# IR_Distance.net
KiCad netlist of a schematic drawn in EAGLE
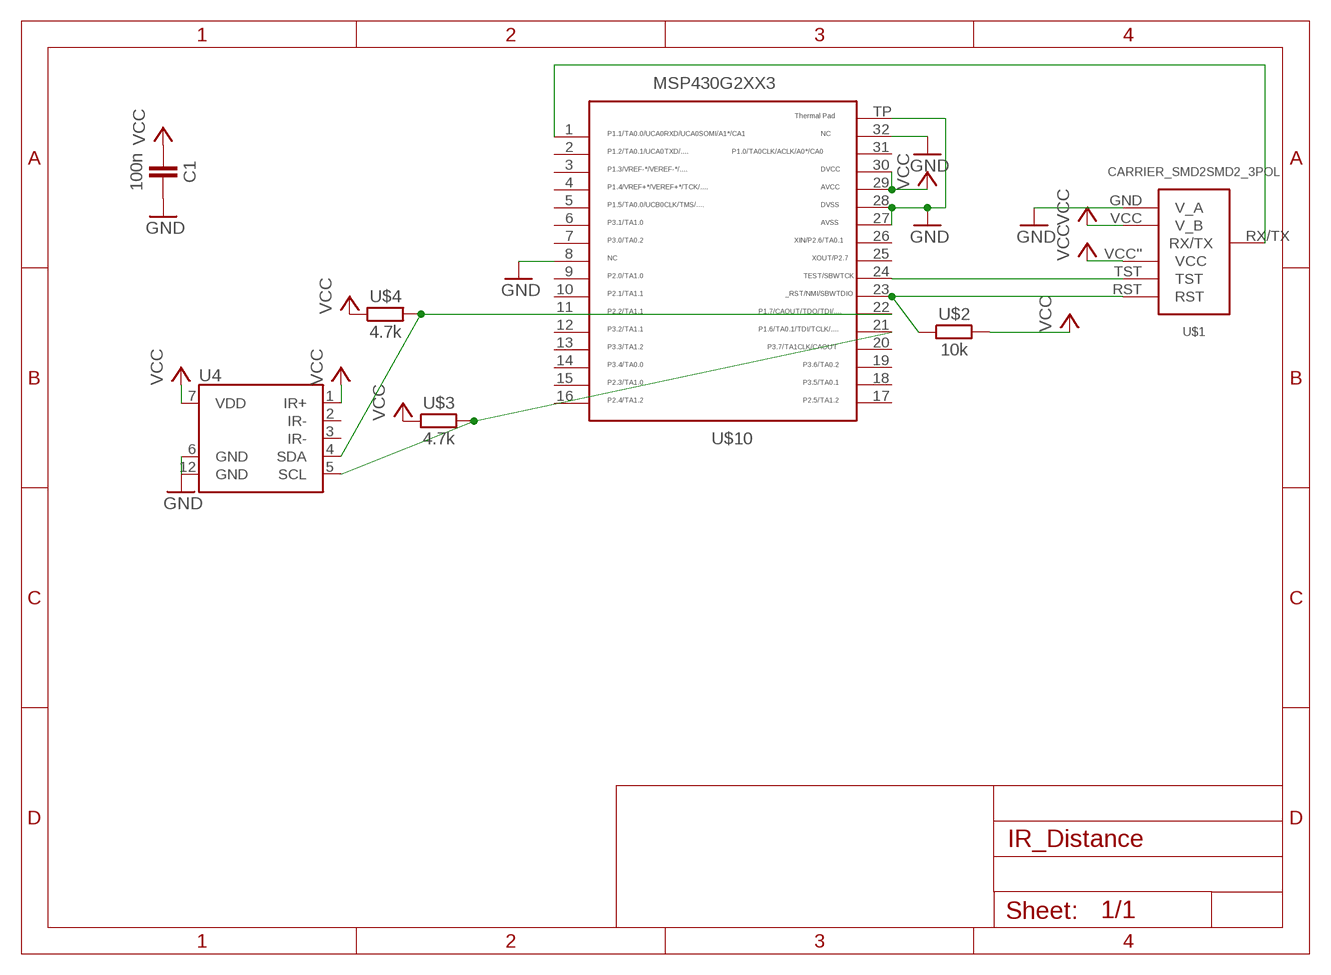
[diagram p0: schematic, sheet 1]

(export (version "E")
  (design (tool "Eeschema 10.0.6"))
  (components
    (comp (ref "C1")
      (value "100n")
      (footprint "eagle-import:603")
      (libsource (lib "eagle-import") (part "CAPACITOR"))
    )
    (comp (ref "U$1")
      (value "CARRIER_SMD2SMD2_3POL")
      (footprint "eagle-import:CARRIER_SMD2_3POL")
      (libsource (lib "eagle-import") (part "CARRIER_SMD2SMD2_3POL"))
    )
    (comp (ref "U$2")
      (value "10k")
      (footprint "eagle-import:603")
      (libsource (lib "eagle-import") (part "RESISTOR0603"))
    )
    (comp (ref "U$3")
      (value "4.7k")
      (footprint "eagle-import:603")
      (libsource (lib "eagle-import") (part "RESISTOR0603"))
    )
    (comp (ref "U$4")
      (value "4.7k")
      (footprint "eagle-import:603")
      (libsource (lib "eagle-import") (part "RESISTOR0603"))
    )
    (comp (ref "U$10")
      (value "MSP430G2553")
      (footprint "eagle-import:QFN32")
      (libsource (lib "eagle-import") (part "MSP430G2553"))
    )
    (comp (ref "U4")
      (value "VCNL4000")
      (footprint "eagle-import:VCNL4000")
      (libsource (lib "eagle-import") (part "VCNL4000"))
    )
  )
  (nets
    (net (code "1") (name "GND") (class "Default")
      (node (ref "C1") (pin "2") (pinfunction "2_2") (pintype "passive"))
      (node (ref "U$1") (pin "GND") (pinfunction "V_A_GND") (pintype "bidirectional"))
      (node (ref "U$10") (pin "27") (pinfunction "27_27") (pintype "bidirectional"))
      (node (ref "U$10") (pin "28") (pinfunction "28_28") (pintype "bidirectional"))
      (node (ref "U$10") (pin "32") (pinfunction "32_32") (pintype "bidirectional"))
      (node (ref "U$10") (pin "8") (pinfunction "8_8") (pintype "bidirectional"))
      (node (ref "U$10") (pin "TP") (pinfunction "TP_TP") (pintype "bidirectional"))
      (node (ref "U4") (pin "12") (pinfunction "GND_12") (pintype "bidirectional"))
      (node (ref "U4") (pin "6") (pinfunction "GND_6") (pintype "bidirectional"))
    )
    (net (code "2") (name "Net-(U$1-PadRST)") (class "Default")
      (node (ref "U$1") (pin "RST") (pinfunction "RST_RST") (pintype "bidirectional"))
      (node (ref "U$10") (pin "23") (pinfunction "23_23") (pintype "bidirectional"))
      (node (ref "U$2") (pin "1") (pinfunction "1_1") (pintype "passive"))
    )
    (net (code "3") (name "Net-(U$1-PadRX{slash}TX)") (class "Default")
      (node (ref "U$1") (pin "RX/TX") (pinfunction "RX/TX_RX/TX") (pintype "bidirectional"))
      (node (ref "U$10") (pin "1") (pinfunction "1_1") (pintype "bidirectional"))
    )
    (net (code "4") (name "Net-(U$1-PadTST)") (class "Default")
      (node (ref "U$1") (pin "TST") (pinfunction "TST_TST") (pintype "bidirectional"))
      (node (ref "U$10") (pin "24") (pinfunction "24_24") (pintype "bidirectional"))
    )
    (net (code "5") (name "Net-(U4-SCL)") (class "Default")
      (node (ref "U$10") (pin "21") (pinfunction "21_21") (pintype "bidirectional"))
      (node (ref "U$3") (pin "2") (pinfunction "2_2") (pintype "passive"))
      (node (ref "U4") (pin "5") (pinfunction "SCL_5") (pintype "bidirectional"))
    )
    (net (code "6") (name "Net-(U4-SDA)") (class "Default")
      (node (ref "U$10") (pin "22") (pinfunction "22_22") (pintype "bidirectional"))
      (node (ref "U$4") (pin "2") (pinfunction "2_2") (pintype "passive"))
      (node (ref "U4") (pin "4") (pinfunction "SDA_4") (pintype "bidirectional"))
    )
    (net (code "7") (name "VCC") (class "Default")
      (node (ref "C1") (pin "1") (pinfunction "1_1") (pintype "passive"))
      (node (ref "U$1") (pin "VCC") (pinfunction "V_B_VCC") (pintype "bidirectional"))
      (node (ref "U$1") (pin "VCC''") (pinfunction "VCC_VCC''") (pintype "bidirectional"))
      (node (ref "U$10") (pin "29") (pinfunction "29_29") (pintype "bidirectional"))
      (node (ref "U$10") (pin "30") (pinfunction "30_30") (pintype "bidirectional"))
      (node (ref "U$2") (pin "2") (pinfunction "2_2") (pintype "passive"))
      (node (ref "U$3") (pin "1") (pinfunction "1_1") (pintype "passive"))
      (node (ref "U$4") (pin "1") (pinfunction "1_1") (pintype "passive"))
      (node (ref "U4") (pin "1") (pinfunction "IR+_1") (pintype "bidirectional"))
      (node (ref "U4") (pin "7") (pinfunction "VDD_7") (pintype "bidirectional"))
    )
    (net (code "8") (name "unconnected-(U$10-Pad2)") (class "Default")
      (node (ref "U$10") (pin "2") (pinfunction "2_2") (pintype "bidirectional"))
    )
    (net (code "9") (name "unconnected-(U$10-Pad3)") (class "Default")
      (node (ref "U$10") (pin "3") (pinfunction "3_3") (pintype "bidirectional"))
    )
    (net (code "10") (name "unconnected-(U$10-Pad4)") (class "Default")
      (node (ref "U$10") (pin "4") (pinfunction "4_4") (pintype "bidirectional"))
    )
    (net (code "11") (name "unconnected-(U$10-Pad5)") (class "Default")
      (node (ref "U$10") (pin "5") (pinfunction "5_5") (pintype "bidirectional"))
    )
    (net (code "12") (name "unconnected-(U$10-Pad6)") (class "Default")
      (node (ref "U$10") (pin "6") (pinfunction "6_6") (pintype "bidirectional"))
    )
    (net (code "13") (name "unconnected-(U$10-Pad7)") (class "Default")
      (node (ref "U$10") (pin "7") (pinfunction "7_7") (pintype "bidirectional"))
    )
    (net (code "14") (name "unconnected-(U$10-Pad9)") (class "Default")
      (node (ref "U$10") (pin "9") (pinfunction "9_9") (pintype "bidirectional"))
    )
    (net (code "15") (name "unconnected-(U$10-Pad10)") (class "Default")
      (node (ref "U$10") (pin "10") (pinfunction "10_10") (pintype "bidirectional"))
    )
    (net (code "16") (name "unconnected-(U$10-Pad11)") (class "Default")
      (node (ref "U$10") (pin "11") (pinfunction "11_11") (pintype "bidirectional"))
    )
    (net (code "17") (name "unconnected-(U$10-Pad12)") (class "Default")
      (node (ref "U$10") (pin "12") (pinfunction "12_12") (pintype "bidirectional"))
    )
    (net (code "18") (name "unconnected-(U$10-Pad13)") (class "Default")
      (node (ref "U$10") (pin "13") (pinfunction "13_13") (pintype "bidirectional"))
    )
    (net (code "19") (name "unconnected-(U$10-Pad14)") (class "Default")
      (node (ref "U$10") (pin "14") (pinfunction "14_14") (pintype "bidirectional"))
    )
    (net (code "20") (name "unconnected-(U$10-Pad15)") (class "Default")
      (node (ref "U$10") (pin "15") (pinfunction "15_15") (pintype "bidirectional"))
    )
    (net (code "21") (name "unconnected-(U$10-Pad16)") (class "Default")
      (node (ref "U$10") (pin "16") (pinfunction "16_16") (pintype "bidirectional"))
    )
    (net (code "22") (name "unconnected-(U$10-Pad17)") (class "Default")
      (node (ref "U$10") (pin "17") (pinfunction "17_17") (pintype "bidirectional"))
    )
    (net (code "23") (name "unconnected-(U$10-Pad18)") (class "Default")
      (node (ref "U$10") (pin "18") (pinfunction "18_18") (pintype "bidirectional"))
    )
    (net (code "24") (name "unconnected-(U$10-Pad19)") (class "Default")
      (node (ref "U$10") (pin "19") (pinfunction "19_19") (pintype "bidirectional"))
    )
    (net (code "25") (name "unconnected-(U$10-Pad20)") (class "Default")
      (node (ref "U$10") (pin "20") (pinfunction "20_20") (pintype "bidirectional"))
    )
    (net (code "26") (name "unconnected-(U$10-Pad25)") (class "Default")
      (node (ref "U$10") (pin "25") (pinfunction "25_25") (pintype "bidirectional"))
    )
    (net (code "27") (name "unconnected-(U$10-Pad26)") (class "Default")
      (node (ref "U$10") (pin "26") (pinfunction "26_26") (pintype "bidirectional"))
    )
    (net (code "28") (name "unconnected-(U$10-Pad31)") (class "Default")
      (node (ref "U$10") (pin "31") (pinfunction "31_31") (pintype "bidirectional"))
    )
    (net (code "29") (name "unconnected-(U4-IR--Pad2)") (class "Default")
      (node (ref "U4") (pin "2") (pinfunction "IR-_2") (pintype "bidirectional"))
    )
    (net (code "30") (name "unconnected-(U4-IR--Pad3)") (class "Default")
      (node (ref "U4") (pin "3") (pinfunction "IR-_3") (pintype "bidirectional"))
    )
  )
)
